# joystick.net
KiCad netlist of a schematic drawn in EasyEDA
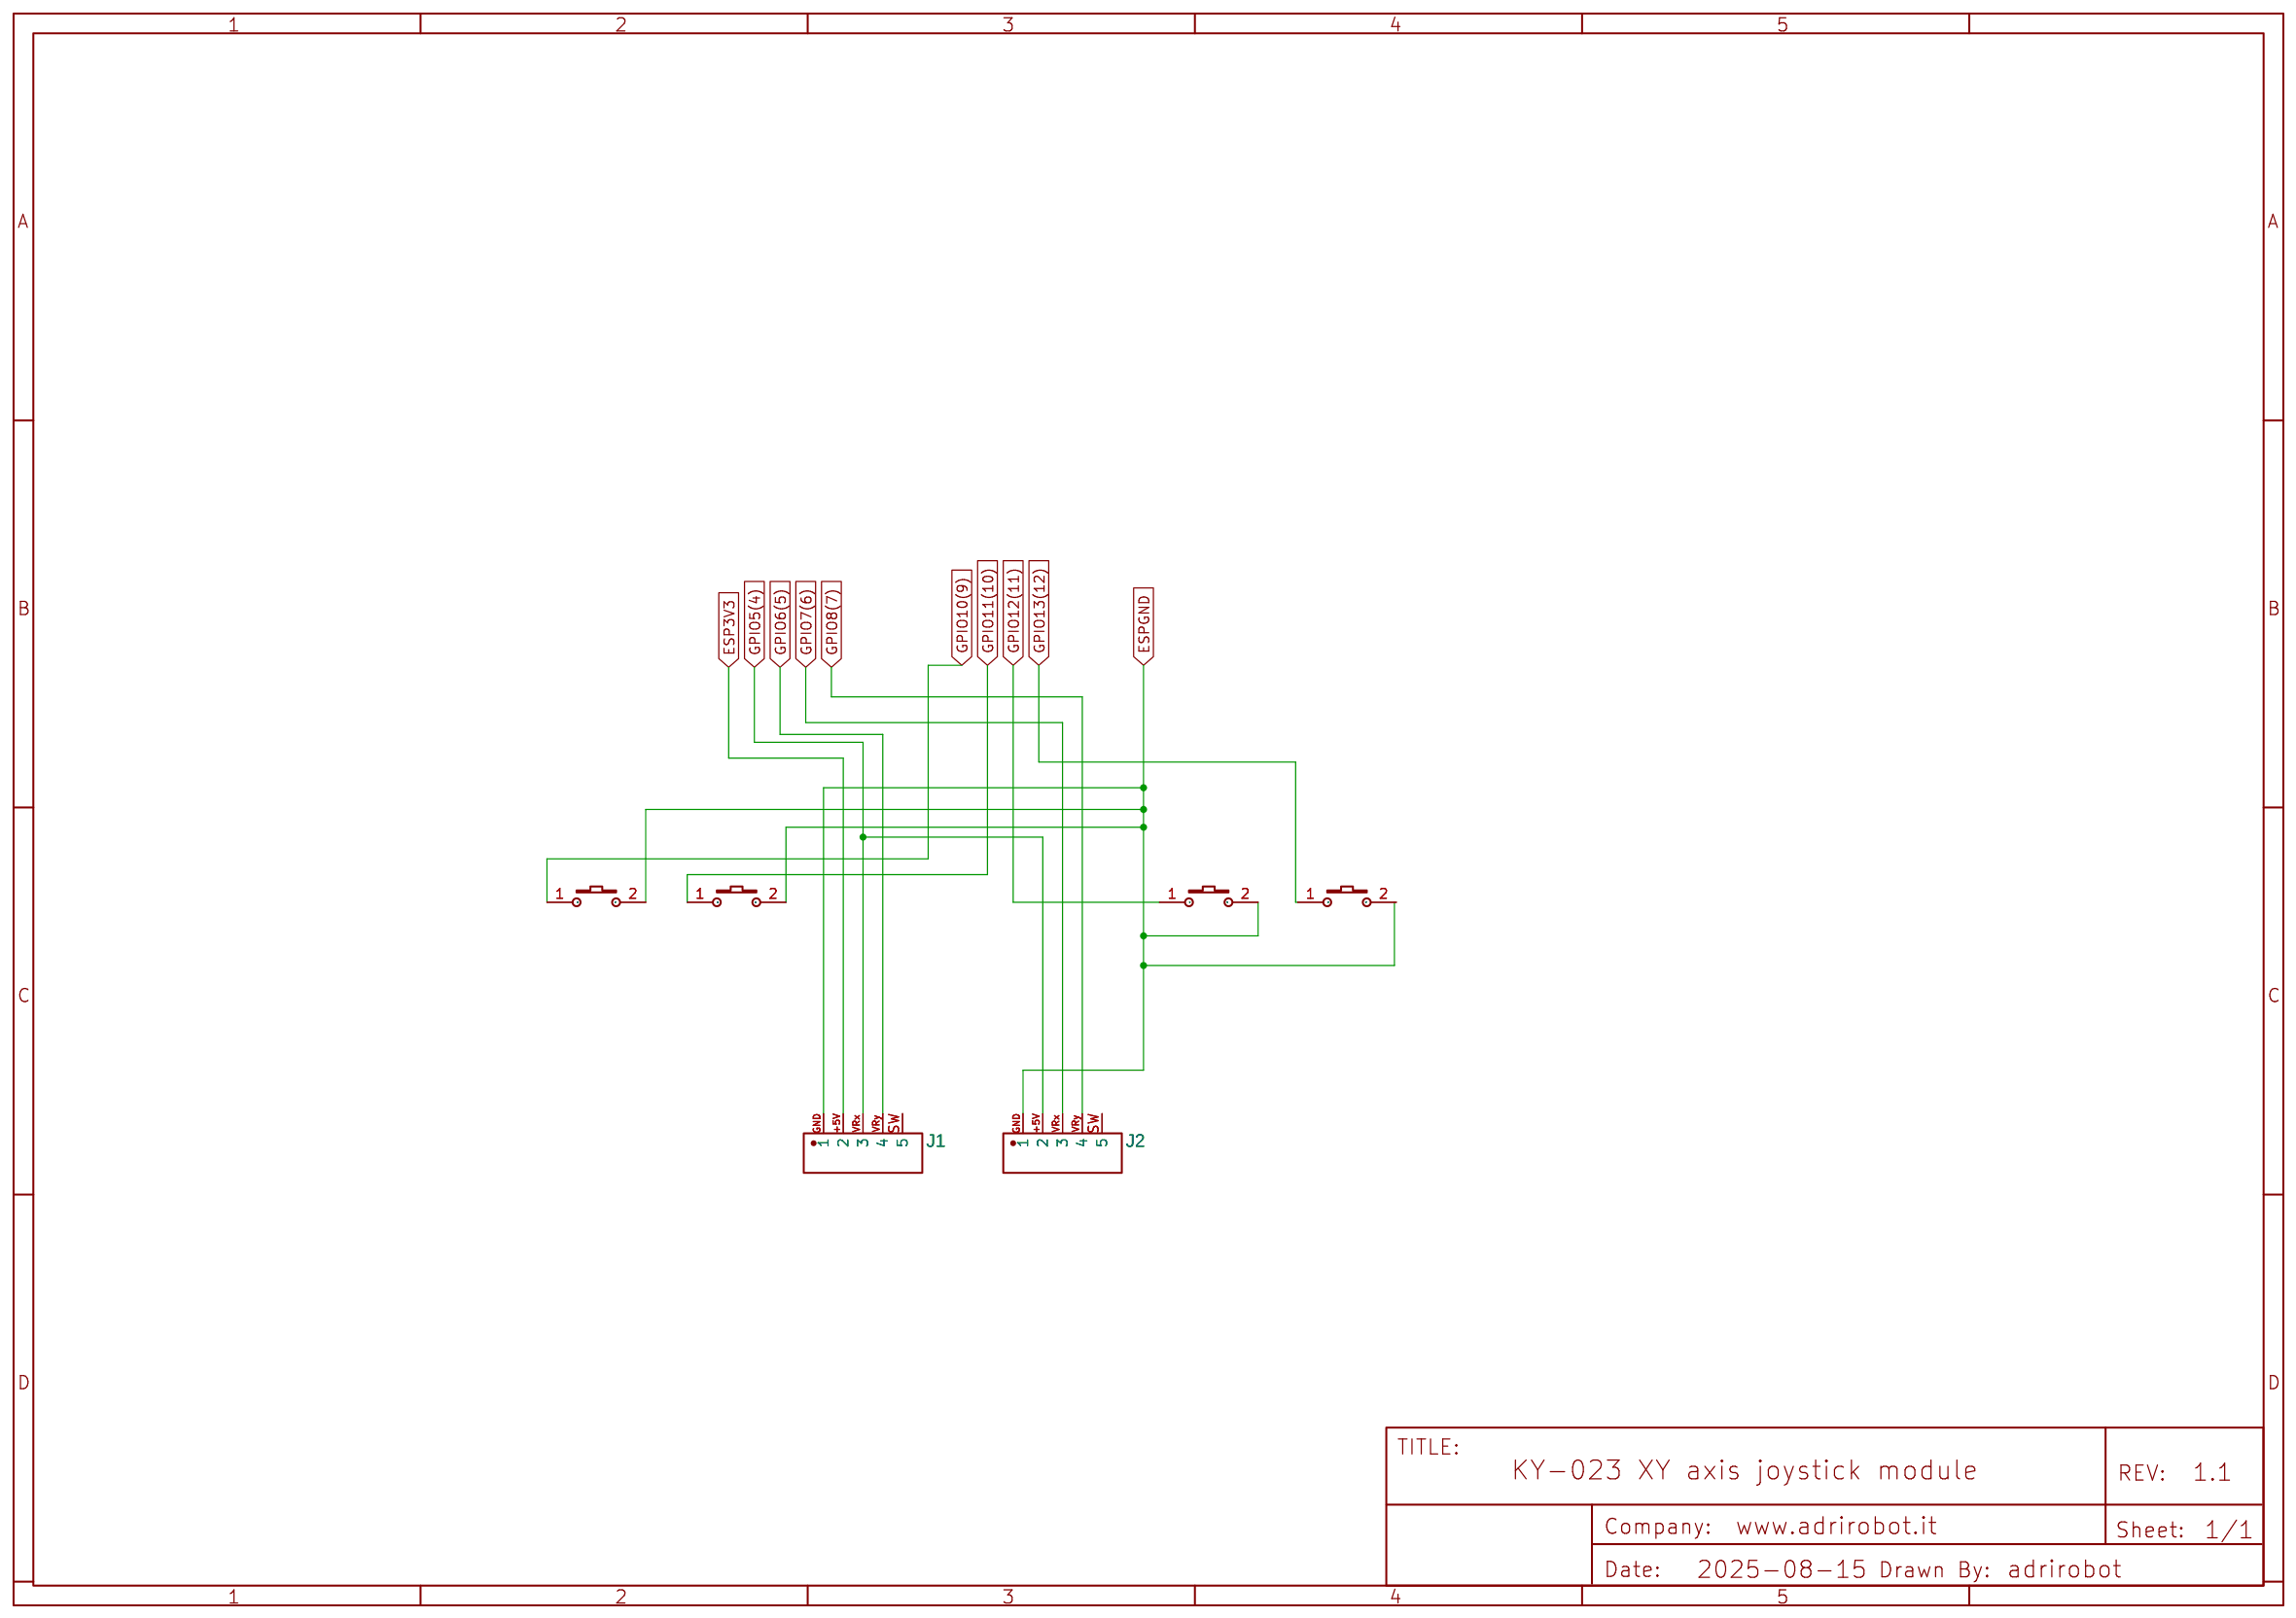
[diagram p0: schematic sheet]

(export (version "E")
  (design (tool "Eeschema 10.0.6"))
  (components
    (comp (ref "J1")
      (value "HX PZ2.54-1X5P WZ-P")
      (fields
        (field (name "Manufacturer Part") "HX PZ2.54-1x5P WZ-P")
        (field (name "Manufacturer") "hanxia(韩下)")
      )
      (libsource (lib "") (part "HX PZ2.54-1X5P WZ-P"))
    )
    (comp (ref "J2")
      (value "HX PZ2.54-1X5P WZ-P")
      (fields
        (field (name "Manufacturer Part") "HX PZ2.54-1x5P WZ-P")
        (field (name "Manufacturer") "hanxia(韩下)")
      )
      (libsource (lib "") (part "HX PZ2.54-1X5P WZ-P"))
    )
    (comp (ref "KEY1")
      (value "K2-3.6×6.1_SMD")
      (fields (field (name "Manufacturer Part") "K2-1107ST-A4SW-06"))
      (libsource (lib "") (part "K2-3.6×6.1_SMD"))
    )
    (comp (ref "KEY2")
      (value "K2-3.6×6.1_SMD")
      (fields (field (name "Manufacturer Part") "K2-1107ST-A4SW-06"))
      (libsource (lib "") (part "K2-3.6×6.1_SMD"))
    )
    (comp (ref "KEY3")
      (value "K2-3.6×6.1_SMD")
      (fields (field (name "Manufacturer Part") "K2-1107ST-A4SW-06"))
      (libsource (lib "") (part "K2-3.6×6.1_SMD"))
    )
    (comp (ref "KEY4")
      (value "K2-3.6×6.1_SMD")
      (fields (field (name "Manufacturer Part") "K2-1107ST-A4SW-06"))
      (libsource (lib "") (part "K2-3.6×6.1_SMD"))
    )
  )
  (nets
    (net (code "1") (name "ESP3V3") (class "Default")
      (node (ref "J1") (pin "+5V") (pinfunction "2_+5V") (pintype "unspecified"))
    )
    (net (code "2") (name "ESPGND") (class "Default")
      (node (ref "J1") (pin "GND") (pinfunction "1_GND") (pintype "unspecified"))
      (node (ref "J2") (pin "GND") (pinfunction "1_GND") (pintype "unspecified"))
      (node (ref "KEY1") (pin "2") (pinfunction "2_2") (pintype "unspecified"))
      (node (ref "KEY2") (pin "2") (pinfunction "2_2") (pintype "unspecified"))
      (node (ref "KEY3") (pin "2") (pinfunction "2_2") (pintype "unspecified"))
    )
    (net (code "3") (name "GPIO5(4)") (class "Default")
      (node (ref "J1") (pin "VRx") (pinfunction "3_VRx") (pintype "unspecified"))
      (node (ref "J2") (pin "+5V") (pinfunction "2_+5V") (pintype "unspecified"))
    )
    (net (code "4") (name "GPIO6(5)") (class "Default")
      (node (ref "J1") (pin "VRy") (pinfunction "4_VRy") (pintype "unspecified"))
    )
    (net (code "5") (name "GPIO7(6)") (class "Default")
      (node (ref "J2") (pin "VRx") (pinfunction "3_VRx") (pintype "unspecified"))
    )
    (net (code "6") (name "GPIO8(7)") (class "Default")
      (node (ref "J2") (pin "VRy") (pinfunction "4_VRy") (pintype "unspecified"))
    )
    (net (code "7") (name "GPIO10(9)") (class "Default")
      (node (ref "KEY1") (pin "1") (pinfunction "1_1") (pintype "unspecified"))
    )
    (net (code "8") (name "GPIO11(10)") (class "Default")
      (node (ref "KEY2") (pin "1") (pinfunction "1_1") (pintype "unspecified"))
    )
    (net (code "9") (name "GPIO12(11)") (class "Default")
      (node (ref "KEY3") (pin "1") (pinfunction "1_1") (pintype "unspecified"))
    )
    (net (code "10") (name "GPIO13(12)") (class "Default")
      (node (ref "KEY4") (pin "1") (pinfunction "1_1") (pintype "unspecified"))
    )
    (net (code "11") (name "unconnected-(J1-5-PadSW)") (class "Default")
      (node (ref "J1") (pin "SW") (pinfunction "5_SW") (pintype "unspecified"))
    )
    (net (code "12") (name "unconnected-(J2-5-PadSW)") (class "Default")
      (node (ref "J2") (pin "SW") (pinfunction "5_SW") (pintype "unspecified"))
    )
    (net (code "13") (name "unconnected-(KEY4-Pad2)") (class "Default")
      (node (ref "KEY4") (pin "2") (pinfunction "2_2") (pintype "unspecified"))
    )
  )
)
